# Power.net
KiCad netlist of a schematic drawn in Altium Designer
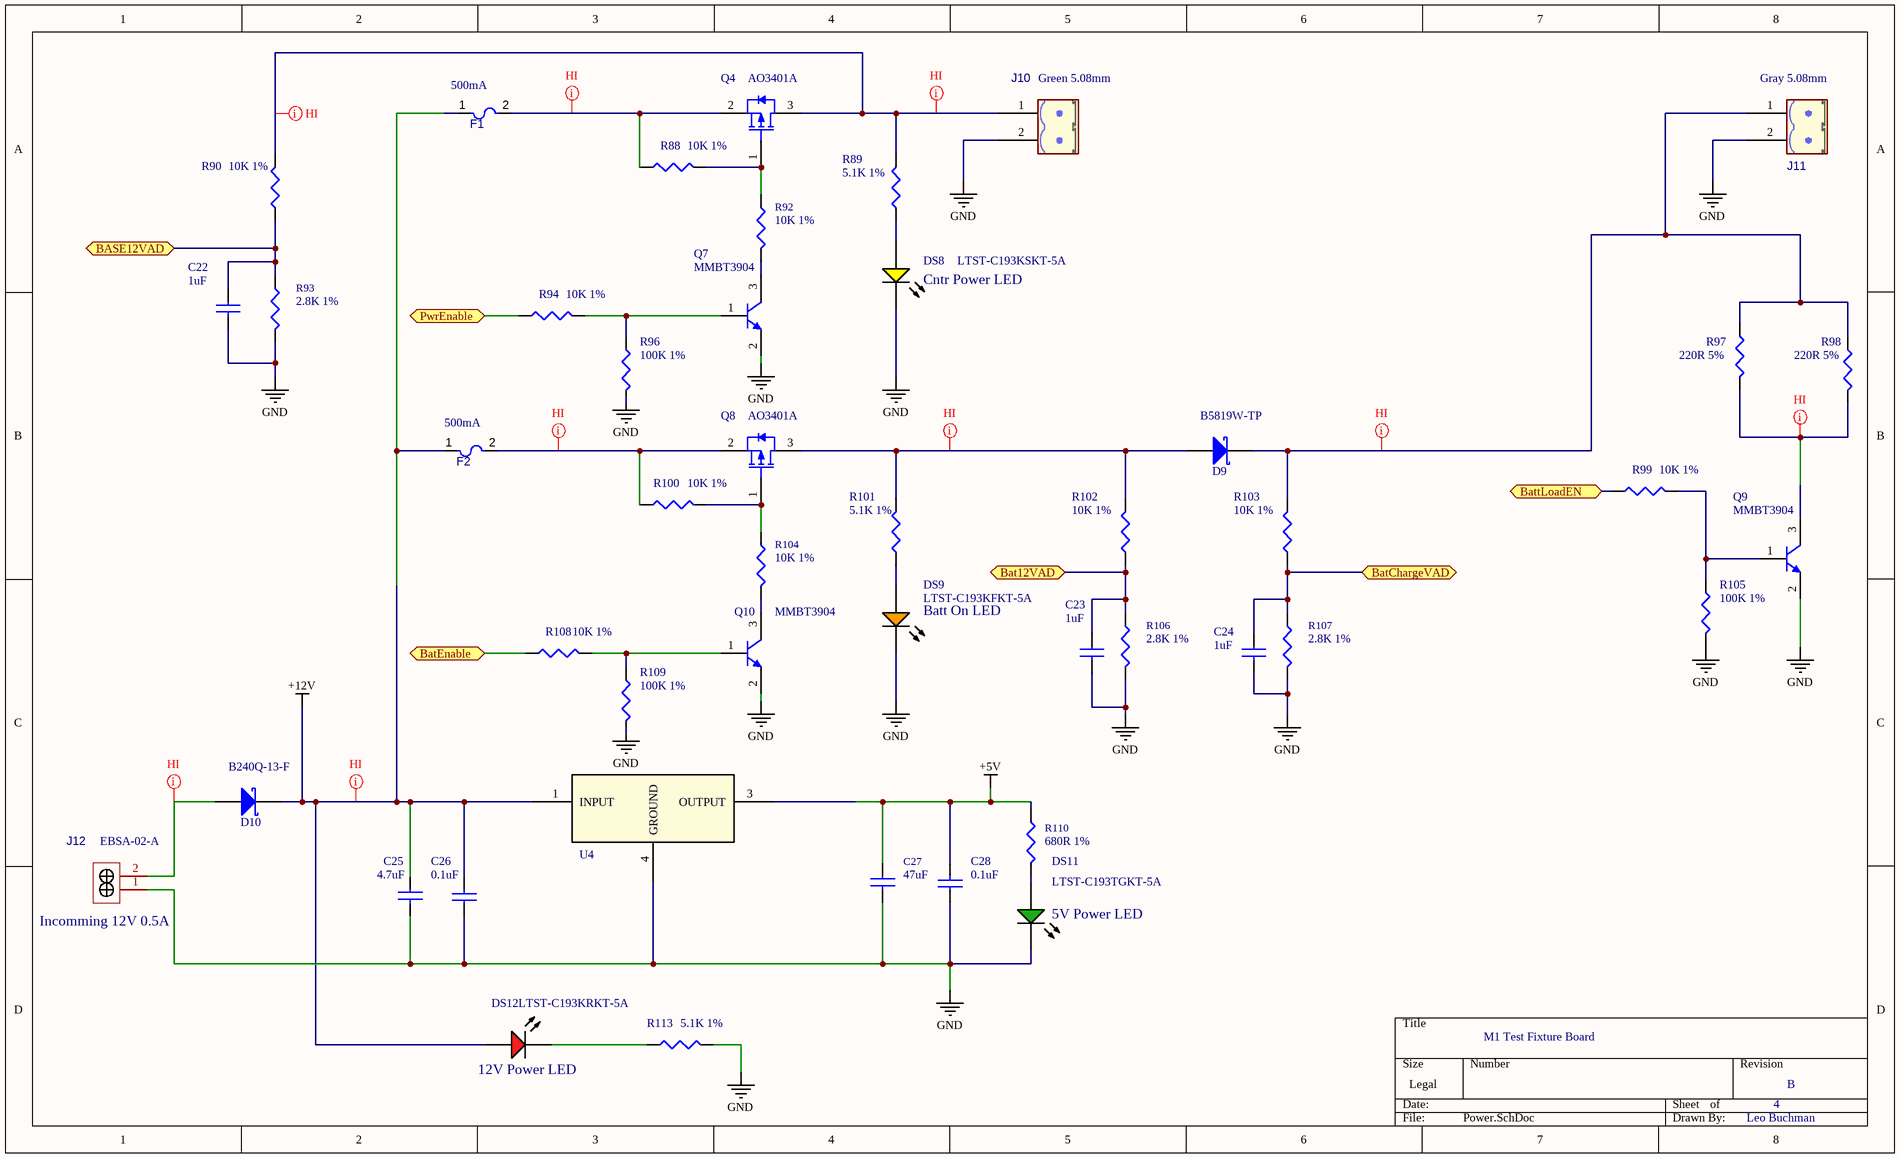
[diagram p0: Power.SchDoc]

(export (version "E")
  (design (tool "Eeschema 10.0.6"))
  (components
    (comp (ref "C22")
      (value "1uF")
      (footprint "C0402")
      (description "CAP CER 1UF 10V Y5V 0402")
      (fields
        (field (name "MANUFACTURER") "KEMET")
        (field (name "MANUFACTURER PART NUMBER") "C0402C105Z8VAC7867")
      )
      (libsource (lib "Leo-Home-SQL-Lib") (part "CAPNP"))
    )
    (comp (ref "C23")
      (value "1uF")
      (footprint "C0402")
      (description "CAP CER 1UF 10V Y5V 0402")
      (fields
        (field (name "MANUFACTURER") "KEMET")
        (field (name "MANUFACTURER PART NUMBER") "C0402C105Z8VAC7867")
      )
      (libsource (lib "Leo-Home-SQL-Lib") (part "CAPNP"))
    )
    (comp (ref "C24")
      (value "1uF")
      (footprint "C0402")
      (description "CAP CER 1UF 10V Y5V 0402")
      (fields
        (field (name "MANUFACTURER") "KEMET")
        (field (name "MANUFACTURER PART NUMBER") "C0402C105Z8VAC7867")
      )
      (libsource (lib "Leo-Home-SQL-Lib") (part "CAPNP"))
    )
    (comp (ref "C25")
      (value "4.7uF")
      (footprint "C0603")
      (description "CAP CER 4.7UF 16V X5R 0603")
      (fields
        (field (name "MANUFACTURER") "Samsung")
        (field (name "MANUFACTURER PART NUMBER") "CL10A475KO8NNNC")
      )
      (libsource (lib "Leo-Home-SQL-Lib") (part "CAPNP"))
    )
    (comp (ref "C26")
      (value "0.1uF")
      (footprint "C0402")
      (description "Cap Ceramic 0.1uF 50V X7R 10% Pad SMD 0402 125C Automotive T/R")
      (fields
        (field (name "MANUFACTURER") "Murata")
        (field (name "MANUFACTURER PART NUMBER") "GRT155R71H104KE01D")
      )
      (libsource (lib "Leo-Home-SQL-Lib") (part "CAPNP"))
    )
    (comp (ref "C27")
      (value "47uF")
      (footprint "C1210")
      (description "CAP CER 47UF 16V X5R 1210")
      (fields
        (field (name "MANUFACTURER") "Murata")
        (field (name "MANUFACTURER PART NUMBER") "GRM32ER61C476ME15L")
      )
      (libsource (lib "Leo-Home-SQL-Lib") (part "CAPNP"))
    )
    (comp (ref "C28")
      (value "0.1uF")
      (footprint "C0402")
      (description "Cap Ceramic 0.1uF 50V X7R 10% Pad SMD 0402 125C Automotive T/R")
      (fields
        (field (name "MANUFACTURER") "Murata")
        (field (name "MANUFACTURER PART NUMBER") "GRT155R71H104KE01D")
      )
      (libsource (lib "Leo-Home-SQL-Lib") (part "CAPNP"))
    )
    (comp (ref "D9")
      (value "B5819W-TP")
      (footprint "MCC-SOD123_V")
      (description "DIODE SCHOTTKY 40V 1A SOD323")
      (fields (field (name "MANUFACTURER") "MCC") (field (name "MANUFACTURER PART NUMBER") "B5819W TP"))
      (libsource (lib "Leo-Home-SQL-Lib") (part "Schottky"))
    )
    (comp (ref "D10")
      (value "B240Q-13-F")
      (footprint "DIODE_DO214AA")
      (description "Rectifier Diode Schottky 40V 2A Automotive 2-Pin SMB T/R")
      (fields (field (name "MANUFACTURER") "Diodes") (field (name "MANUFACTURER_1") "MCC"))
      (libsource (lib "Leo-Home-SQL-Lib") (part "Schottky"))
    )
    (comp (ref "DS8")
      (value "LTST-C193KSKT-5A")
      (footprint "LED-YELLOW_0603")
      (description "LED Yellow CLEAR 0603 SMD")
      (fields (field (name "MANUFACTURER") "Vishay Lite-On") (field (name "LCSC PART NUMBER") "C72038"))
      (libsource (lib "Leo-Home-SQL-Lib") (part "LED-Yellow"))
    )
    (comp (ref "DS9")
      (value "LTST-C193KFKT-5A")
      (footprint "LED-ORANGE_0603")
      (description "LED Orange CLEAR 0603 SMD")
      (fields (field (name "MANUFACTURER") "Vishay Lite-On") (field (name "MANUFACTURER_1") "Rohm"))
      (libsource (lib "Leo-Home-SQL-Lib") (part "LED-Orange"))
    )
    (comp (ref "DS11")
      (value "LTST-C193TGKT-5A")
      (footprint "LED-GREEN_0603")
      (description "LED Green CLEAR 0603 SMD")
      (fields (field (name "MANUFACTURER") "Vishay Lite-On") (field (name "LCSC PART NUMBER") "C72043"))
      (libsource (lib "Leo-Home-SQL-Lib") (part "LED-Green"))
    )
    (comp (ref "DS12")
      (value "LTST-C193KRKT-5A")
      (footprint "LED-RED_0603")
      (description "LED RED CLEAR 0603 SMD")
      (fields (field (name "MANUFACTURER") "Vishay Lite-On") (field (name "MANUFACTURER_1") "Broadcom Avago"))
      (libsource (lib "Leo-Home-SQL-Lib") (part "LED-Red"))
    )
    (comp (ref "F1")
      (value "500mA")
      (footprint "FUSE_F050-2")
      (description "15VDC 500mA")
      (fields (field (name "MANUFACTURER") "Bourns") (field (name "MANUFACTURER PART NUMBER") "MF-MSMF050-2"))
      (libsource (lib "Leo-Home-SQL-Lib") (part "FusePTC"))
    )
    (comp (ref "F2")
      (value "500mA")
      (footprint "FUSE_F050-2")
      (description "15VDC 500mA")
      (fields (field (name "MANUFACTURER") "Bourns") (field (name "MANUFACTURER PART NUMBER") "MF-MSMF050-2"))
      (libsource (lib "Leo-Home-SQL-Lib") (part "FusePTC"))
    )
    (comp (ref "J10")
      (value "Green 5.08mm")
      (footprint "Conn_5433668")
      (description "Pluggable Term Blocks BCH-508HS- 2 GN 5.08")
      (fields
        (field (name "MANUFACTURER") "Phoenix Contact")
        (field (name "MANUFACTURER PART NUMBER") "5442002")
      )
      (libsource (lib "Leo-Home-SQL-Lib") (part "CN_5MM08_02POS_HEADER_RTA_GRAY"))
    )
    (comp (ref "J11")
      (value "Gray 5.08mm")
      (footprint "Conn_5442002")
      (description "Pluggable Term Blocks BCH-508HS- 2 GR 5.08")
      (fields
        (field (name "MANUFACTURER") "Phoenix Contact")
        (field (name "MANUFACTURER PART NUMBER") "5433668")
      )
      (libsource (lib "Leo-Home-SQL-Lib") (part "CN_5MM08_02POS_HEADER_RTA_GRN"))
    )
    (comp (ref "J12")
      (value "EBSA-02-A")
      (footprint "CONN-TH_2P-P3.50_JL15EDGRC-35002G01")
      (description "Conn Header Right angle 3.5 pitch 2P")
      (fields (field (name "MANUFACTURER") "Adam Equipment") (field (name "LCSC PART NUMBER") "C409115"))
      (libsource (lib "Leo-Home-SQL-Lib") (part "term_block_2"))
    )
    (comp (ref "Q4")
      (value "AO3401A")
      (footprint "AO-SOT-23-3L_V")
      (description "Mosfet P-channel 30V 4A SOT23-3")
      (fields
        (field (name "MANUFACTURER") "Alpha & Omega Semiconductor")
        (field (name "MANUFACTURER PART NUMBER") "AO3401AL")
      )
      (libsource (lib "Leo-Home-SQL-Lib") (part "MOSFET-P"))
    )
    (comp (ref "Q7")
      (value "MMBT3904")
      (footprint "sot23-3")
      (description "Trans GP BJT NPN 60V 0.2A 350mW Automotive 3-Pin SOT-23 T/R")
      (fields (field (name "MANUFACTURER") "ON Semiconductor / Fairchild") (field (name "POWER") "225mW"))
      (libsource (lib "Leo-Home-SQL-Lib") (part "BJT-NPN"))
    )
    (comp (ref "Q8")
      (value "AO3401A")
      (footprint "AO-SOT-23-3L_V")
      (description "Mosfet P-channel 30V 4A SOT23-3")
      (fields
        (field (name "MANUFACTURER") "Alpha & Omega Semiconductor")
        (field (name "MANUFACTURER PART NUMBER") "AO3401AL")
      )
      (libsource (lib "Leo-Home-SQL-Lib") (part "MOSFET-P"))
    )
    (comp (ref "Q9")
      (value "MMBT3904")
      (footprint "sot23-3")
      (description "Trans GP BJT NPN 60V 0.2A 350mW Automotive 3-Pin SOT-23 T/R")
      (fields (field (name "MANUFACTURER") "ON Semiconductor / Fairchild") (field (name "POWER") "225mW"))
      (libsource (lib "Leo-Home-SQL-Lib") (part "BJT-NPN"))
    )
    (comp (ref "Q10")
      (value "MMBT3904")
      (footprint "sot23-3")
      (description "Trans GP BJT NPN 60V 0.2A 350mW Automotive 3-Pin SOT-23 T/R")
      (fields (field (name "MANUFACTURER") "ON Semiconductor / Fairchild") (field (name "POWER") "225mW"))
      (libsource (lib "Leo-Home-SQL-Lib") (part "BJT-NPN"))
    )
    (comp (ref "R88")
      (value "10K 1%")
      (footprint "R0402")
      (description "Thick Film 0402 10K OHM 1% 1/16W 0402")
      (fields
        (field (name "MANUFACTURER") "Yageo")
        (field (name "MANUFACTURER PART NUMBER") "RC0402FR-0710KP")
      )
      (libsource (lib "Leo-Home-SQL-Lib") (part "Resistor"))
    )
    (comp (ref "R89")
      (value "5.1K 1%")
      (footprint "R0402")
      (description "Thick Film 0402 5.1K Ohm 1% 1/16W 0402")
      (fields
        (field (name "MANUFACTURER") "Stackpole Electronics")
        (field (name "MANUFACTURER PART NUMBER") "RMCF0402FT5K10")
      )
      (libsource (lib "Leo-Home-SQL-Lib") (part "Resistor"))
    )
    (comp (ref "R90")
      (value "10K 1%")
      (footprint "R0402")
      (description "Thick Film 0402 10K OHM 1% 1/16W 0402")
      (fields
        (field (name "MANUFACTURER") "Yageo")
        (field (name "MANUFACTURER PART NUMBER") "RC0402FR-0710KP")
      )
      (libsource (lib "Leo-Home-SQL-Lib") (part "Resistor"))
    )
    (comp (ref "R92")
      (value "10K 1%")
      (footprint "R0402")
      (description "Thick Film 0402 10K OHM 1% 1/16W 0402")
      (fields
        (field (name "MANUFACTURER") "Yageo")
        (field (name "MANUFACTURER PART NUMBER") "RC0402FR-0710KP")
      )
      (libsource (lib "Leo-Home-SQL-Lib") (part "Resistor"))
    )
    (comp (ref "R93")
      (value "2.8K 1%")
      (footprint "R0402")
      (description "Thick Film 0402 2.8K Ohm 1% 0.063W ±100ppm/°C Molded SMD Paper T/R")
      (fields
        (field (name "MANUFACTURER") "Stackpole Electronics")
        (field (name "MANUFACTURER PART NUMBER") "RMCF0402FT2K80")
      )
      (libsource (lib "Leo-Home-SQL-Lib") (part "Resistor"))
    )
    (comp (ref "R94")
      (value "10K 1%")
      (footprint "R0402")
      (description "Thick Film 0402 10K OHM 1% 1/16W 0402")
      (fields
        (field (name "MANUFACTURER") "Yageo")
        (field (name "MANUFACTURER PART NUMBER") "RC0402FR-0710KP")
      )
      (libsource (lib "Leo-Home-SQL-Lib") (part "Resistor"))
    )
    (comp (ref "R96")
      (value "100K 1%")
      (footprint "R0402")
      (description "Thick Film 0402 100K OHM 1% 1/16W 0402")
      (fields
        (field (name "MANUFACTURER") "Stackpole Electronics")
        (field (name "MANUFACTURER PART NUMBER") "RMCF0402FT100K")
      )
      (libsource (lib "Leo-Home-SQL-Lib") (part "Resistor"))
    )
    (comp (ref "R97")
      (value "220R 5%")
      (footprint "RESC6331X75N")
      (description "Thick Film  220 OHM 5% 1W 2512")
      (fields
        (field (name "MANUFACTURER") "Stackpole Electronics")
        (field (name "MANUFACTURER PART NUMBER") "RMCF2512JT220R")
      )
      (libsource (lib "Leo-Home-SQL-Lib") (part "Resistor"))
    )
    (comp (ref "R98")
      (value "220R 5%")
      (footprint "RESC6331X75N")
      (description "Thick Film  220 OHM 5% 1W 2512")
      (fields
        (field (name "MANUFACTURER") "Stackpole Electronics")
        (field (name "MANUFACTURER PART NUMBER") "RMCF2512JT220R")
      )
      (libsource (lib "Leo-Home-SQL-Lib") (part "Resistor"))
    )
    (comp (ref "R99")
      (value "10K 1%")
      (footprint "R0402")
      (description "Thick Film 0402 10K OHM 1% 1/16W 0402")
      (fields
        (field (name "MANUFACTURER") "Yageo")
        (field (name "MANUFACTURER PART NUMBER") "RC0402FR-0710KP")
      )
      (libsource (lib "Leo-Home-SQL-Lib") (part "Resistor"))
    )
    (comp (ref "R100")
      (value "10K 1%")
      (footprint "R0402")
      (description "Thick Film 0402 10K OHM 1% 1/16W 0402")
      (fields
        (field (name "MANUFACTURER") "Yageo")
        (field (name "MANUFACTURER PART NUMBER") "RC0402FR-0710KP")
      )
      (libsource (lib "Leo-Home-SQL-Lib") (part "Resistor"))
    )
    (comp (ref "R101")
      (value "5.1K 1%")
      (footprint "R0402")
      (description "Thick Film 0402 5.1K Ohm 1% 1/16W 0402")
      (fields
        (field (name "MANUFACTURER") "Stackpole Electronics")
        (field (name "MANUFACTURER PART NUMBER") "RMCF0402FT5K10")
      )
      (libsource (lib "Leo-Home-SQL-Lib") (part "Resistor"))
    )
    (comp (ref "R102")
      (value "10K 1%")
      (footprint "R0402")
      (description "Thick Film 0402 10K OHM 1% 1/16W 0402")
      (fields
        (field (name "MANUFACTURER") "Yageo")
        (field (name "MANUFACTURER PART NUMBER") "RC0402FR-0710KP")
      )
      (libsource (lib "Leo-Home-SQL-Lib") (part "Resistor"))
    )
    (comp (ref "R103")
      (value "10K 1%")
      (footprint "R0402")
      (description "Thick Film 0402 10K OHM 1% 1/16W 0402")
      (fields
        (field (name "MANUFACTURER") "Yageo")
        (field (name "MANUFACTURER PART NUMBER") "RC0402FR-0710KP")
      )
      (libsource (lib "Leo-Home-SQL-Lib") (part "Resistor"))
    )
    (comp (ref "R104")
      (value "10K 1%")
      (footprint "R0402")
      (description "Thick Film 0402 10K OHM 1% 1/16W 0402")
      (fields
        (field (name "MANUFACTURER") "Yageo")
        (field (name "MANUFACTURER PART NUMBER") "RC0402FR-0710KP")
      )
      (libsource (lib "Leo-Home-SQL-Lib") (part "Resistor"))
    )
    (comp (ref "R105")
      (value "100K 1%")
      (footprint "R0402")
      (description "Thick Film 0402 100K OHM 1% 1/16W 0402")
      (fields
        (field (name "MANUFACTURER") "Stackpole Electronics")
        (field (name "MANUFACTURER PART NUMBER") "RMCF0402FT100K")
      )
      (libsource (lib "Leo-Home-SQL-Lib") (part "Resistor"))
    )
    (comp (ref "R106")
      (value "2.8K 1%")
      (footprint "R0402")
      (description "Thick Film 0402 2.8K Ohm 1% 0.063W ±100ppm/°C Molded SMD Paper T/R")
      (fields
        (field (name "MANUFACTURER") "Stackpole Electronics")
        (field (name "MANUFACTURER PART NUMBER") "RMCF0402FT2K80")
      )
      (libsource (lib "Leo-Home-SQL-Lib") (part "Resistor"))
    )
    (comp (ref "R107")
      (value "2.8K 1%")
      (footprint "R0402")
      (description "Thick Film 0402 2.8K Ohm 1% 0.063W ±100ppm/°C Molded SMD Paper T/R")
      (fields
        (field (name "MANUFACTURER") "Stackpole Electronics")
        (field (name "MANUFACTURER PART NUMBER") "RMCF0402FT2K80")
      )
      (libsource (lib "Leo-Home-SQL-Lib") (part "Resistor"))
    )
    (comp (ref "R108")
      (value "10K 1%")
      (footprint "R0402")
      (description "Thick Film 0402 10K OHM 1% 1/16W 0402")
      (fields
        (field (name "MANUFACTURER") "Yageo")
        (field (name "MANUFACTURER PART NUMBER") "RC0402FR-0710KP")
      )
      (libsource (lib "Leo-Home-SQL-Lib") (part "Resistor"))
    )
    (comp (ref "R109")
      (value "100K 1%")
      (footprint "R0402")
      (description "Thick Film 0402 100K OHM 1% 1/16W 0402")
      (fields
        (field (name "MANUFACTURER") "Stackpole Electronics")
        (field (name "MANUFACTURER PART NUMBER") "RMCF0402FT100K")
      )
      (libsource (lib "Leo-Home-SQL-Lib") (part "Resistor"))
    )
    (comp (ref "R110")
      (value "680R 1%")
      (footprint "R0402")
      (description "Thick Film 0402 680 Ohm 1% 0.063W(1/16W) ±100ppm/C Pad SMD Automotive T/R")
      (fields
        (field (name "MANUFACTURER") "Stackpole Electronics")
        (field (name "MANUFACTURER PART NUMBER") "RMCF0402FT680R")
      )
      (libsource (lib "Leo-Home-SQL-Lib") (part "Resistor"))
    )
    (comp (ref "R113")
      (value "5.1K 1%")
      (footprint "R0402")
      (description "Thick Film 0402 5.1K Ohm 1% 1/16W 0402")
      (fields
        (field (name "MANUFACTURER") "Stackpole Electronics")
        (field (name "MANUFACTURER PART NUMBER") "RMCF0402FT5K10")
      )
      (libsource (lib "Leo-Home-SQL-Lib") (part "Resistor"))
    )
    (comp (ref "U4")
      (value "L7805CD2T-TR")
      (footprint "VREG_L7805ACD2T")
      (description "IC REG LDO 5V 1.5A D2PAK")
      (fields (field (name "MANUFACTURER") "STMicroelectronics") (field (name "LCSC PART NUMBER") "C15077"))
      (libsource (lib "Leo-Home-SQL-Lib") (part "L7805CD2T-TR"))
    )
  )
  (nets
    (net (code "1") (name "+5V") (class "Default")
      (node (ref "C27") (pin "1") (pinfunction "1_1") (pintype "passive"))
      (node (ref "C28") (pin "2") (pinfunction "2_2") (pintype "passive"))
      (node (ref "R110") (pin "1") (pinfunction "1_1") (pintype "passive"))
      (node (ref "U4") (pin "3") (pinfunction "OUTPUT_3") (pintype "power_in"))
    )
    (net (code "2") (name "+12V") (class "Default")
      (node (ref "C25") (pin "1") (pinfunction "1_1") (pintype "passive"))
      (node (ref "C26") (pin "2") (pinfunction "2_2") (pintype "passive"))
      (node (ref "D10") (pin "2") (pinfunction "K_2") (pintype "passive"))
      (node (ref "DS12") (pin "1") (pinfunction "A_1") (pintype "passive"))
      (node (ref "F1") (pin "1") (pinfunction "1_1") (pintype "passive"))
      (node (ref "F2") (pin "1") (pinfunction "1_1") (pintype "passive"))
      (node (ref "U4") (pin "1") (pinfunction "INPUT_1") (pintype "power_in"))
    )
    (net (code "3") (name "/BASE12VAD") (class "Default")
      (node (ref "C22") (pin "1") (pinfunction "1_1") (pintype "passive"))
      (node (ref "R90") (pin "1") (pinfunction "1_1") (pintype "passive"))
      (node (ref "R93") (pin "1") (pinfunction "1_1") (pintype "passive"))
    )
    (net (code "4") (name "/Bat12VAD") (class "Default")
      (node (ref "C23") (pin "1") (pinfunction "1_1") (pintype "passive"))
      (node (ref "R102") (pin "1") (pinfunction "1_1") (pintype "passive"))
      (node (ref "R106") (pin "1") (pinfunction "1_1") (pintype "passive"))
    )
    (net (code "5") (name "/BatChargeVAD") (class "Default")
      (node (ref "C24") (pin "1") (pinfunction "1_1") (pintype "passive"))
      (node (ref "R103") (pin "1") (pinfunction "1_1") (pintype "passive"))
      (node (ref "R107") (pin "1") (pinfunction "1_1") (pintype "passive"))
    )
    (net (code "6") (name "/BatEnable") (class "Default")
      (node (ref "R108") (pin "1") (pinfunction "1_1") (pintype "passive"))
    )
    (net (code "7") (name "/BattLoadEN") (class "Default")
      (node (ref "R99") (pin "1") (pinfunction "1_1") (pintype "passive"))
    )
    (net (code "8") (name "/PwrEnable") (class "Default")
      (node (ref "R94") (pin "1") (pinfunction "1_1") (pintype "passive"))
    )
    (net (code "9") (name "GND") (class "Default")
      (node (ref "C22") (pin "2") (pinfunction "2_2") (pintype "passive"))
      (node (ref "C23") (pin "2") (pinfunction "2_2") (pintype "passive"))
      (node (ref "C24") (pin "2") (pinfunction "2_2") (pintype "passive"))
      (node (ref "C25") (pin "2") (pinfunction "2_2") (pintype "passive"))
      (node (ref "C26") (pin "1") (pinfunction "1_1") (pintype "passive"))
      (node (ref "C27") (pin "2") (pinfunction "2_2") (pintype "passive"))
      (node (ref "C28") (pin "1") (pinfunction "1_1") (pintype "passive"))
      (node (ref "DS11") (pin "2") (pinfunction "K_2") (pintype "passive"))
      (node (ref "DS8") (pin "2") (pinfunction "K_2") (pintype "passive"))
      (node (ref "DS9") (pin "2") (pinfunction "K_2") (pintype "passive"))
      (node (ref "J10") (pin "2") (pinfunction "2_2") (pintype "passive"))
      (node (ref "J11") (pin "2") (pinfunction "2_2") (pintype "passive"))
      (node (ref "J12") (pin "1") (pinfunction "1_1") (pintype "passive"))
      (node (ref "Q10") (pin "2") (pinfunction "E_2") (pintype "passive"))
      (node (ref "Q7") (pin "2") (pinfunction "E_2") (pintype "passive"))
      (node (ref "Q9") (pin "2") (pinfunction "E_2") (pintype "passive"))
      (node (ref "R105") (pin "2") (pinfunction "2_2") (pintype "passive"))
      (node (ref "R106") (pin "2") (pinfunction "2_2") (pintype "passive"))
      (node (ref "R107") (pin "2") (pinfunction "2_2") (pintype "passive"))
      (node (ref "R109") (pin "2") (pinfunction "2_2") (pintype "passive"))
      (node (ref "R113") (pin "2") (pinfunction "2_2") (pintype "passive"))
      (node (ref "R93") (pin "2") (pinfunction "2_2") (pintype "passive"))
      (node (ref "R96") (pin "2") (pinfunction "2_2") (pintype "passive"))
      (node (ref "U4") (pin "4") (pinfunction "GROUND_4") (pintype "passive"))
    )
    (net (code "10") (name "Net-(D9-A)") (class "Default")
      (node (ref "D9") (pin "1") (pinfunction "A_1") (pintype "passive"))
      (node (ref "Q8") (pin "3") (pinfunction "DRAIN_3") (pintype "passive"))
      (node (ref "R101") (pin "2") (pinfunction "2_2") (pintype "passive"))
      (node (ref "R102") (pin "2") (pinfunction "2_2") (pintype "passive"))
    )
    (net (code "11") (name "Net-(D9-K)") (class "Default")
      (node (ref "D9") (pin "2") (pinfunction "K_2") (pintype "passive"))
      (node (ref "J11") (pin "1") (pinfunction "1_1") (pintype "passive"))
      (node (ref "R103") (pin "2") (pinfunction "2_2") (pintype "passive"))
      (node (ref "R97") (pin "1") (pinfunction "1_1") (pintype "passive"))
      (node (ref "R98") (pin "1") (pinfunction "1_1") (pintype "passive"))
    )
    (net (code "12") (name "Net-(D10-A)") (class "Default")
      (node (ref "D10") (pin "1") (pinfunction "A_1") (pintype "passive"))
      (node (ref "J12") (pin "2") (pinfunction "2_2") (pintype "passive"))
    )
    (net (code "13") (name "Net-(DS8-A)") (class "Default")
      (node (ref "DS8") (pin "1") (pinfunction "A_1") (pintype "passive"))
      (node (ref "R89") (pin "1") (pinfunction "1_1") (pintype "passive"))
    )
    (net (code "14") (name "Net-(DS9-A)") (class "Default")
      (node (ref "DS9") (pin "1") (pinfunction "A_1") (pintype "passive"))
      (node (ref "R101") (pin "1") (pinfunction "1_1") (pintype "passive"))
    )
    (net (code "15") (name "Net-(DS11-A)") (class "Default")
      (node (ref "DS11") (pin "1") (pinfunction "A_1") (pintype "passive"))
      (node (ref "R110") (pin "2") (pinfunction "2_2") (pintype "passive"))
    )
    (net (code "16") (name "Net-(DS12-K)") (class "Default")
      (node (ref "DS12") (pin "2") (pinfunction "K_2") (pintype "passive"))
      (node (ref "R113") (pin "1") (pinfunction "1_1") (pintype "passive"))
    )
    (net (code "17") (name "Net-(Q4-DRAIN)") (class "Default")
      (node (ref "J10") (pin "1") (pinfunction "1_1") (pintype "passive"))
      (node (ref "Q4") (pin "3") (pinfunction "DRAIN_3") (pintype "passive"))
      (node (ref "R89") (pin "2") (pinfunction "2_2") (pintype "passive"))
      (node (ref "R90") (pin "2") (pinfunction "2_2") (pintype "passive"))
    )
    (net (code "18") (name "Net-(Q4-GATE)") (class "Default")
      (node (ref "Q4") (pin "1") (pinfunction "GATE_1") (pintype "passive"))
      (node (ref "R88") (pin "2") (pinfunction "2_2") (pintype "passive"))
      (node (ref "R92") (pin "1") (pinfunction "1_1") (pintype "passive"))
    )
    (net (code "19") (name "Net-(Q4-SOURCE)") (class "Default")
      (node (ref "F1") (pin "2") (pinfunction "2_2") (pintype "passive"))
      (node (ref "Q4") (pin "2") (pinfunction "SOURCE_2") (pintype "passive"))
      (node (ref "R88") (pin "1") (pinfunction "1_1") (pintype "passive"))
    )
    (net (code "20") (name "Net-(Q7-B)") (class "Default")
      (node (ref "Q7") (pin "1") (pinfunction "B_1") (pintype "passive"))
      (node (ref "R94") (pin "2") (pinfunction "2_2") (pintype "passive"))
      (node (ref "R96") (pin "1") (pinfunction "1_1") (pintype "passive"))
    )
    (net (code "21") (name "Net-(Q7-C)") (class "Default")
      (node (ref "Q7") (pin "3") (pinfunction "C_3") (pintype "passive"))
      (node (ref "R92") (pin "2") (pinfunction "2_2") (pintype "passive"))
    )
    (net (code "22") (name "Net-(Q8-GATE)") (class "Default")
      (node (ref "Q8") (pin "1") (pinfunction "GATE_1") (pintype "passive"))
      (node (ref "R100") (pin "2") (pinfunction "2_2") (pintype "passive"))
      (node (ref "R104") (pin "1") (pinfunction "1_1") (pintype "passive"))
    )
    (net (code "23") (name "Net-(Q8-SOURCE)") (class "Default")
      (node (ref "F2") (pin "2") (pinfunction "2_2") (pintype "passive"))
      (node (ref "Q8") (pin "2") (pinfunction "SOURCE_2") (pintype "passive"))
      (node (ref "R100") (pin "1") (pinfunction "1_1") (pintype "passive"))
    )
    (net (code "24") (name "Net-(Q9-B)") (class "Default")
      (node (ref "Q9") (pin "1") (pinfunction "B_1") (pintype "passive"))
      (node (ref "R105") (pin "1") (pinfunction "1_1") (pintype "passive"))
      (node (ref "R99") (pin "2") (pinfunction "2_2") (pintype "passive"))
    )
    (net (code "25") (name "Net-(Q9-C)") (class "Default")
      (node (ref "Q9") (pin "3") (pinfunction "C_3") (pintype "passive"))
      (node (ref "R97") (pin "2") (pinfunction "2_2") (pintype "passive"))
      (node (ref "R98") (pin "2") (pinfunction "2_2") (pintype "passive"))
    )
    (net (code "26") (name "Net-(Q10-B)") (class "Default")
      (node (ref "Q10") (pin "1") (pinfunction "B_1") (pintype "passive"))
      (node (ref "R108") (pin "2") (pinfunction "2_2") (pintype "passive"))
      (node (ref "R109") (pin "1") (pinfunction "1_1") (pintype "passive"))
    )
    (net (code "27") (name "Net-(Q10-C)") (class "Default")
      (node (ref "Q10") (pin "3") (pinfunction "C_3") (pintype "passive"))
      (node (ref "R104") (pin "2") (pinfunction "2_2") (pintype "passive"))
    )
  )
)
